# design.net
KiCad netlist of a schematic drawn in Altium Designer
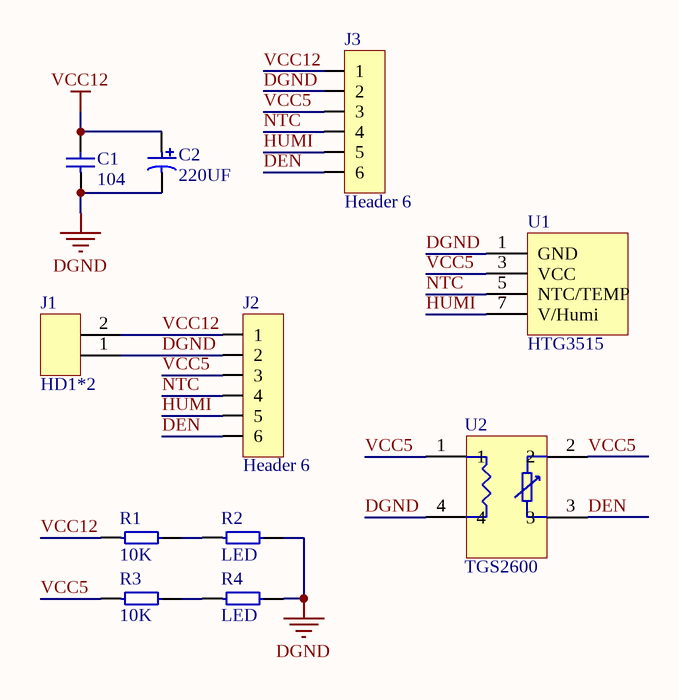
[diagram p0: 浓度探头.SchDoc]

(export (version "E")
  (design (tool "Eeschema 10.0.6"))
  (components
    (comp (ref "C1") (value "104") (footprint "0805C") (libsource (lib "basic") (part "CAP")))
    (comp (ref "C2") (value "220UF") (footprint "RB 2.5/6.3") (libsource (lib "basic") (part "CAP-POL2")))
    (comp (ref "J1") (value "HD1*2") (footprint "XH2.54-2P") (libsource (lib "接插件") (part "HD1*2")))
    (comp (ref "J2") (value "Header 6") (footprint "HDR1X6") (libsource (lib "Connectors") (part "Header 6")))
    (comp (ref "J3") (value "Header 6") (footprint "HDR1X6") (libsource (lib "Connectors") (part "Header 6")))
    (comp (ref "R1") (value "10K") (footprint "0805") (libsource (lib "基本元件") (part "Res")))
    (comp (ref "R2") (value "LED") (footprint "0805") (libsource (lib "基本元件") (part "Res")))
    (comp (ref "R3") (value "10K") (footprint "0805") (libsource (lib "基本元件") (part "Res")))
    (comp (ref "R4") (value "LED") (footprint "0805") (libsource (lib "基本元件") (part "Res")))
    (comp (ref "U1") (value "HTG3515") (footprint "HD2*4-2.0") (libsource (lib "常用芯片") (part "HTG3515")))
    (comp (ref "U2") (value "TGS2600") (footprint "TGS2600") (libsource (lib "常用芯片") (part "TGS2600")))
  )
  (nets
    (net (code "1") (name "/DEN") (class "Default")
      (node (ref "J2") (pin "6") (pinfunction "6_6") (pintype "passive"))
      (node (ref "J3") (pin "6") (pinfunction "6_6") (pintype "passive"))
      (node (ref "U2") (pin "3") (pinfunction "3_3") (pintype "passive"))
    )
    (net (code "2") (name "/HUMI") (class "Default")
      (node (ref "J2") (pin "5") (pinfunction "5_5") (pintype "passive"))
      (node (ref "J3") (pin "5") (pinfunction "5_5") (pintype "passive"))
      (node (ref "U1") (pin "7") (pinfunction "V/Humi_7") (pintype "passive"))
    )
    (net (code "3") (name "/NTC") (class "Default")
      (node (ref "J2") (pin "4") (pinfunction "4_4") (pintype "passive"))
      (node (ref "J3") (pin "4") (pinfunction "4_4") (pintype "passive"))
      (node (ref "U1") (pin "5") (pinfunction "NTC/TEMP_5") (pintype "passive"))
    )
    (net (code "4") (name "/VCC5") (class "Default")
      (node (ref "J2") (pin "3") (pinfunction "3_3") (pintype "passive"))
      (node (ref "J3") (pin "3") (pinfunction "3_3") (pintype "passive"))
      (node (ref "R3") (pin "1") (pinfunction "1_1") (pintype "passive"))
      (node (ref "U1") (pin "3") (pinfunction "VCC_3") (pintype "passive"))
      (node (ref "U2") (pin "1") (pinfunction "1_1") (pintype "passive"))
      (node (ref "U2") (pin "2") (pinfunction "2_2") (pintype "passive"))
    )
    (net (code "5") (name "DGND") (class "Default")
      (node (ref "C1") (pin "1") (pinfunction "1_1") (pintype "passive"))
      (node (ref "C2") (pin "1") (pinfunction "1_1") (pintype "passive"))
      (node (ref "J1") (pin "1") (pinfunction "1_1") (pintype "passive"))
      (node (ref "J2") (pin "2") (pinfunction "2_2") (pintype "passive"))
      (node (ref "J3") (pin "2") (pinfunction "2_2") (pintype "passive"))
      (node (ref "R2") (pin "2") (pinfunction "2_2") (pintype "passive"))
      (node (ref "R4") (pin "2") (pinfunction "2_2") (pintype "passive"))
      (node (ref "U1") (pin "1") (pinfunction "GND_1") (pintype "passive"))
      (node (ref "U2") (pin "4") (pinfunction "4_4") (pintype "passive"))
    )
    (net (code "6") (name "Net-(R1-Pad2)") (class "Default")
      (node (ref "R1") (pin "2") (pinfunction "2_2") (pintype "passive"))
      (node (ref "R2") (pin "1") (pinfunction "1_1") (pintype "passive"))
    )
    (net (code "7") (name "Net-(R3-Pad2)") (class "Default")
      (node (ref "R3") (pin "2") (pinfunction "2_2") (pintype "passive"))
      (node (ref "R4") (pin "1") (pinfunction "1_1") (pintype "passive"))
    )
    (net (code "8") (name "VCC12") (class "Default")
      (node (ref "C1") (pin "2") (pinfunction "2_2") (pintype "passive"))
      (node (ref "C2") (pin "2") (pinfunction "2_2") (pintype "passive"))
      (node (ref "J1") (pin "2") (pinfunction "2_2") (pintype "passive"))
      (node (ref "J2") (pin "1") (pinfunction "1_1") (pintype "passive"))
      (node (ref "J3") (pin "1") (pinfunction "1_1") (pintype "passive"))
      (node (ref "R1") (pin "1") (pinfunction "1_1") (pintype "passive"))
    )
  )
)
